# BoardTop.net
KiCad netlist of a schematic drawn in Altium Designer
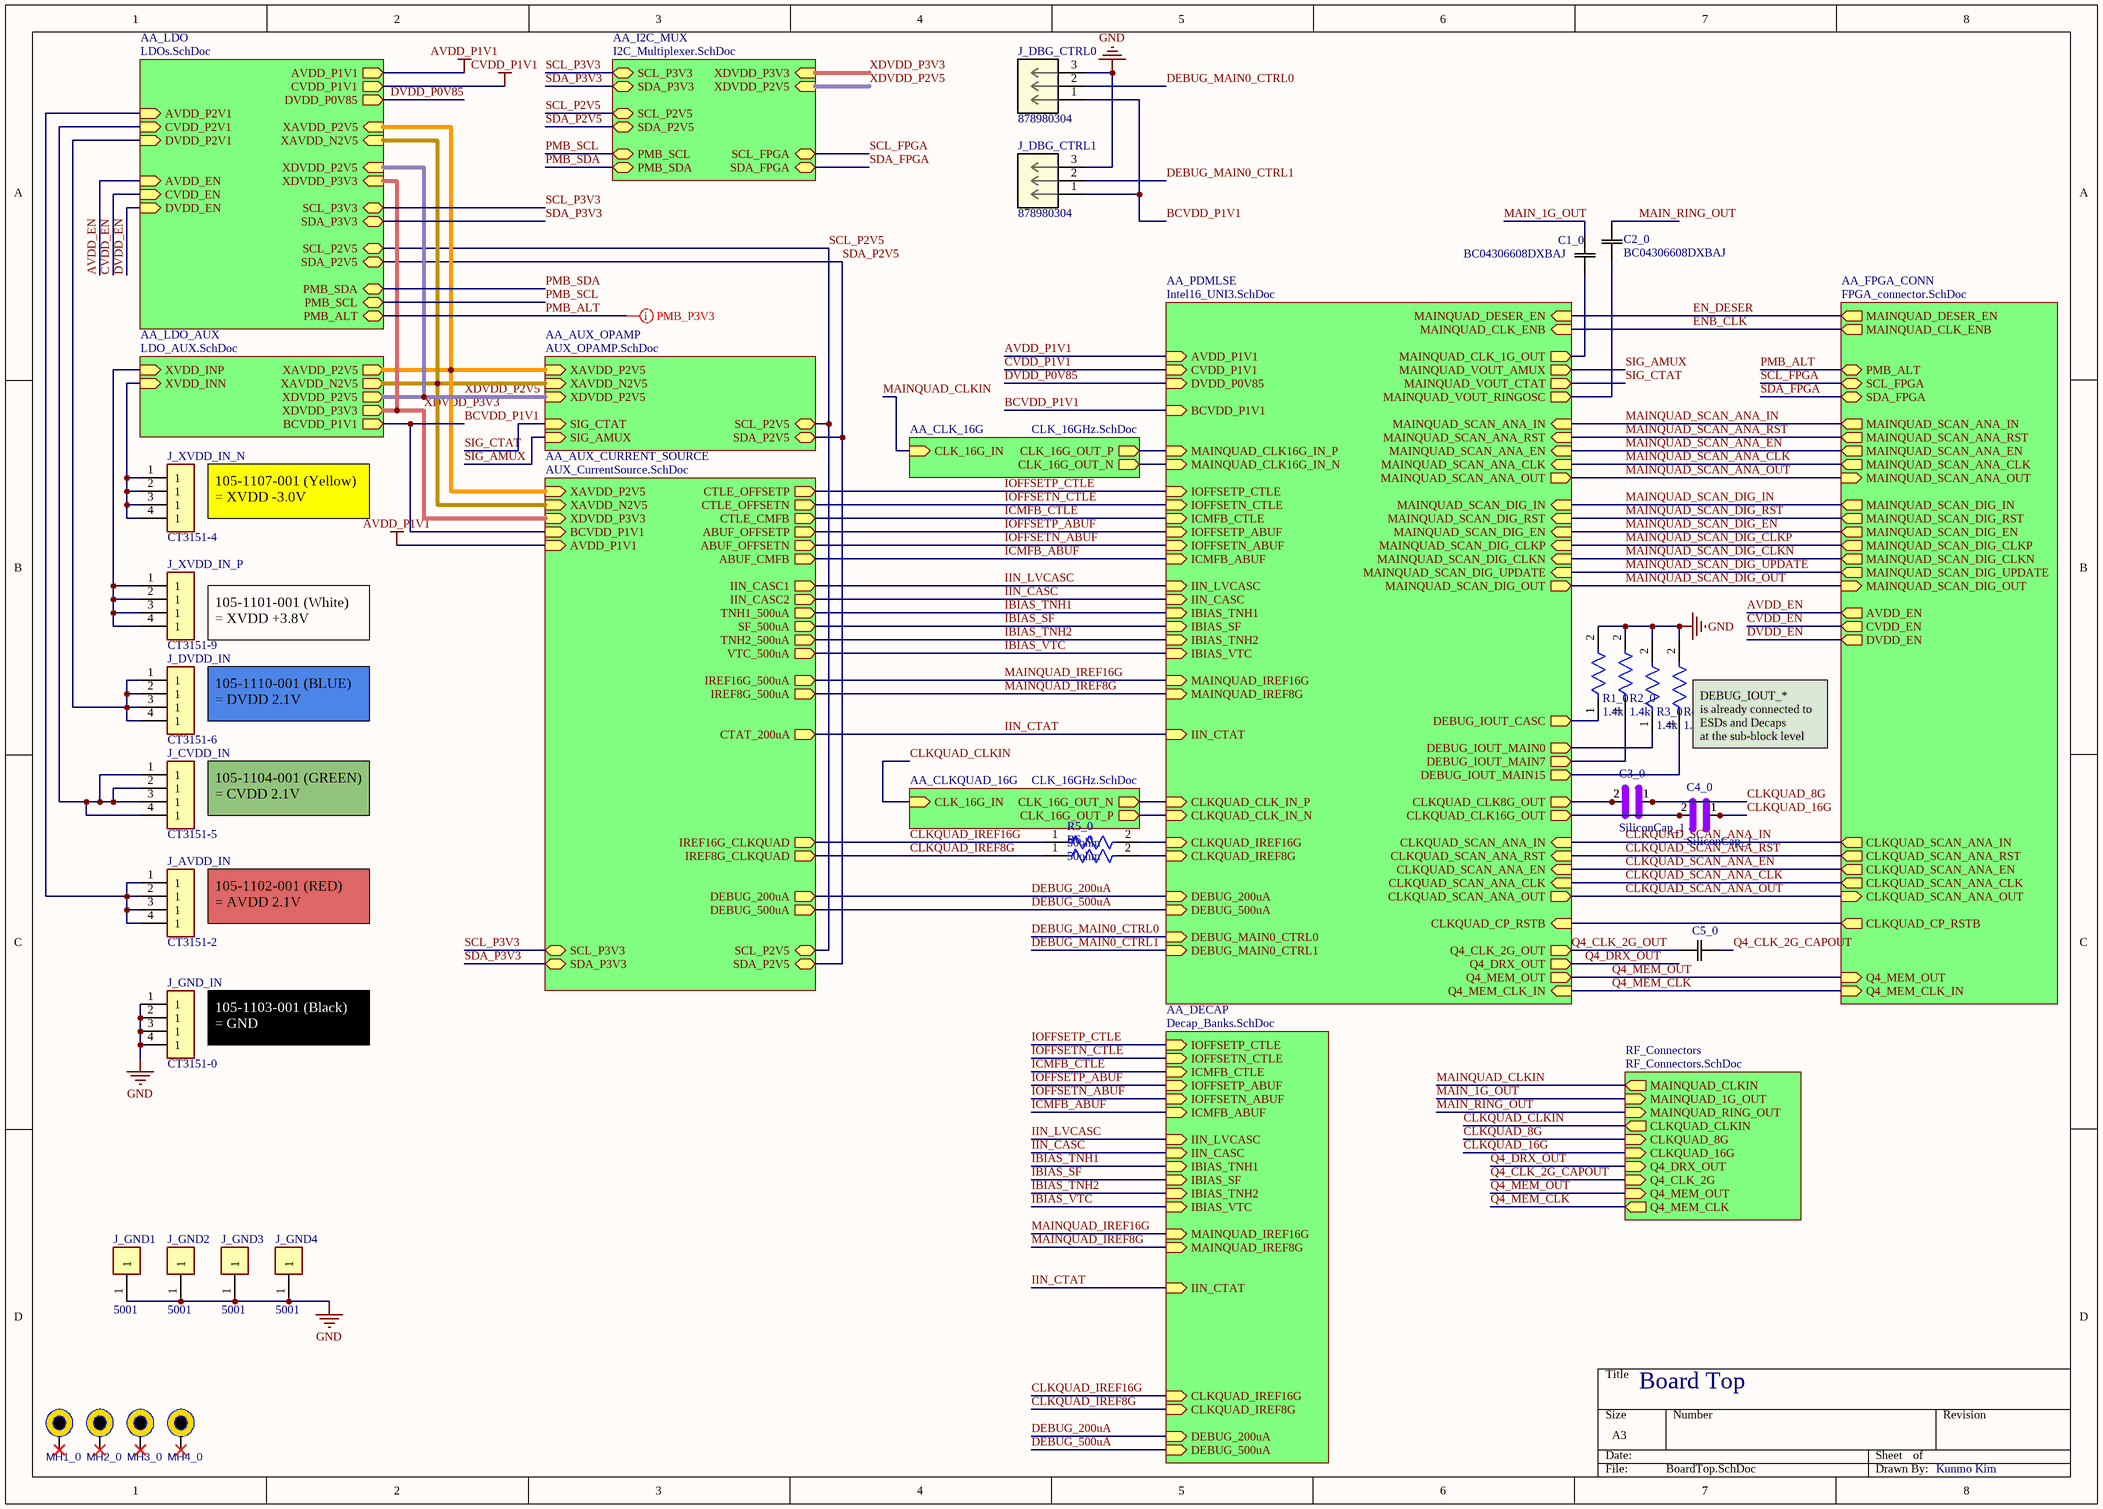
[diagram p0: BoardTop.SchDoc]

(export (version "E")
  (design (tool "Eeschema 10.0.6"))
  (components
    (comp (ref "C1_0")
      (value "BC04306608DXBAJ")
      (footprint "CAP_BC04_VIS")
      (description "No Description Available")
      (libsource (lib "BC04306608DXBAJ") (part "BC04306608DXBAJ"))
    )
    (comp (ref "C2_0")
      (value "BC04306608DXBAJ")
      (footprint "CAP_BC04_VIS")
      (description "No Description Available")
      (libsource (lib "BC04306608DXBAJ") (part "BC04306608DXBAJ"))
    )
    (comp (ref "C3_0")
      (value "SiliconCap_1")
      (footprint "0201-NOSILK")
      (description "939114492510-T3S from Murata")
      (libsource (lib "DC_Blocker") (part "SiliconCap_1"))
    )
    (comp (ref "C4_0")
      (value "SiliconCap_1")
      (footprint "0201-NOSILK")
      (description "939114492510-T3S from Murata")
      (libsource (lib "DC_Blocker") (part "SiliconCap_1"))
    )
    (comp (ref "C5_0")
      (value "BC04306608DXBAJ")
      (footprint "CAP_BC04_VIS")
      (description "No Description Available")
      (libsource (lib "BC04306608DXBAJ") (part "BC04306608DXBAJ"))
    )
    (comp (ref "J_AVDD_IN")
      (value "CT3151-2")
      (footprint "CALTEST_CT3151-2")
      (description "Banana Jack Connector Standard Banana Solder Red")
      (fields (field (name "MF") "Cal Test"))
      (libsource (lib "CT3151-2") (part "CT3151-2"))
    )
    (comp (ref "J_CVDD_IN")
      (value "CT3151-5")
      (footprint "CALTEST_CT3151-2")
      (description "Banana Jack Connector Standard Banana Solder Green")
      (fields (field (name "MF") "Cal Test") (field (name "MP") "CT3151-2"))
      (libsource (lib "CT3151-2") (part "CT3151-5"))
    )
    (comp (ref "J_DBG_CTRL0")
      (value "878980304")
      (footprint "CONN03_87898_M-5p84_MOL")
      (description "No Description Available")
      (libsource (lib "878980304") (part "878980304"))
    )
    (comp (ref "J_DBG_CTRL1")
      (value "878980304")
      (footprint "CONN03_87898_M-5p84_MOL")
      (description "No Description Available")
      (libsource (lib "878980304") (part "878980304"))
    )
    (comp (ref "J_DVDD_IN")
      (value "CT3151-6")
      (footprint "CALTEST_CT3151-2")
      (description "Banana Jack Connector Standard Banana Solder Green")
      (fields (field (name "MF") "Cal Test") (field (name "MP") "CT3151-2"))
      (libsource (lib "CT3151-2") (part "CT3151-6"))
    )
    (comp (ref "J_GND1")
      (value "5001")
      (footprint "FP-5001-MFG")
      (description "PC TEST POINT MINIATURE BLACK")
      (libsource (lib "TP_5001") (part "CMP-2000-05181-2"))
    )
    (comp (ref "J_GND2")
      (value "5001")
      (footprint "FP-5001-MFG")
      (description "PC TEST POINT MINIATURE BLACK")
      (libsource (lib "TP_5001") (part "CMP-2000-05181-2"))
    )
    (comp (ref "J_GND3")
      (value "5001")
      (footprint "FP-5001-MFG")
      (description "PC TEST POINT MINIATURE BLACK")
      (libsource (lib "TP_5001") (part "CMP-2000-05181-2"))
    )
    (comp (ref "J_GND4")
      (value "5001")
      (footprint "FP-5001-MFG")
      (description "PC TEST POINT MINIATURE BLACK")
      (libsource (lib "TP_5001") (part "CMP-2000-05181-2"))
    )
    (comp (ref "J_GND_IN")
      (value "CT3151-0")
      (footprint "CALTEST_CT3151-0")
      (description "Banana Jack Connector Standard Banana Solder Black")
      (fields (field (name "MF") "Cal Test") (field (name "MP") "CT3151-2"))
      (libsource (lib "CT3151-2") (part "CT3151-0"))
    )
    (comp (ref "J_XVDD_IN_N")
      (value "CT3151-4")
      (footprint "CALTEST_CT3151-2")
      (description "Banana Jack Connector Standard Banana Solder Yellow")
      (fields (field (name "MF") "Cal Test") (field (name "MP") "CT3151-2"))
      (libsource (lib "CT3151-2") (part "CT3151-4"))
    )
    (comp (ref "J_XVDD_IN_P")
      (value "CT3151-9")
      (footprint "CALTEST_CT3151-2")
      (description "Banana Jack Connector Standard Banana Solder White")
      (fields (field (name "MF") "Cal Test") (field (name "MP") "CT3151-2"))
      (libsource (lib "CT3151-2") (part "CT3151-9"))
    )
    (comp (ref "MH1_0")
      (value "MTG")
      (footprint "MTG-3.2/6.5-PTH")
      (description "Mounting hole")
      (libsource (lib "BRK8305") (part "MTG"))
    )
    (comp (ref "MH2_0")
      (value "MTG")
      (footprint "MTG-3.2/6.5-PTH")
      (description "Mounting hole")
      (libsource (lib "BRK8305") (part "MTG"))
    )
    (comp (ref "MH3_0")
      (value "MTG")
      (footprint "MTG-3.2/6.5-PTH")
      (description "Mounting hole")
      (libsource (lib "BRK8305") (part "MTG"))
    )
    (comp (ref "MH4_0")
      (value "MTG")
      (footprint "MTG-3.2/6.5-PTH")
      (description "Mounting hole")
      (libsource (lib "BRK8305") (part "MTG"))
    )
    (comp (ref "R1_0")
      (value "1.4k")
      (footprint "FP-CRCW1206-e3-IPC_B")
      (description "RES Thick Film, 1.4kΩ, 1%, 0.25W, 100ppm/°C, 1206")
      (fields (field (name "TOLERANCE") "1%"))
      (libsource (lib "resistor_1206_1p4k") (part "CMP-2003-01885-2"))
    )
    (comp (ref "R2_0")
      (value "1.4k")
      (footprint "FP-CRCW1206-e3-IPC_B")
      (description "RES Thick Film, 1.4kΩ, 1%, 0.25W, 100ppm/°C, 1206")
      (fields (field (name "TOLERANCE") "1%"))
      (libsource (lib "resistor_1206_1p4k") (part "CMP-2003-01885-2"))
    )
    (comp (ref "R3_0")
      (value "1.4k")
      (footprint "FP-CRCW1206-e3-IPC_B")
      (description "RES Thick Film, 1.4kΩ, 1%, 0.25W, 100ppm/°C, 1206")
      (fields (field (name "TOLERANCE") "1%"))
      (libsource (lib "resistor_1206_1p4k") (part "CMP-2003-01885-2"))
    )
    (comp (ref "R4_0")
      (value "1.4k")
      (footprint "FP-CRCW1206-e3-IPC_B")
      (description "RES Thick Film, 1.4kΩ, 1%, 0.25W, 100ppm/°C, 1206")
      (fields (field (name "TOLERANCE") "1%"))
      (libsource (lib "resistor_1206_1p4k") (part "CMP-2003-01885-2"))
    )
    (comp (ref "R5_0")
      (value "50ohm")
      (footprint "FP-RT0402-0_35-IPC_A")
      (fields (field (name "TOLERANCE") "0.1%"))
      (libsource (lib "resistor_50ohm_0402_0p1ptol") (part "1029c3af85768c4190bb7ad29bc67b5"))
    )
    (comp (ref "R6_0")
      (value "50ohm")
      (footprint "FP-RT0402-0_35-IPC_A")
      (fields (field (name "TOLERANCE") "0.1%"))
      (libsource (lib "resistor_50ohm_0402_0p1ptol") (part "1029c3af85768c4190bb7ad29bc67b5"))
    )
  )
  (nets
    (net (code "2") (name "/AVDD_P2V1") (class "Default")
      (node (ref "J_AVDD_IN") (pin "1") (pinfunction "1_1") (pintype "passive"))
      (node (ref "J_AVDD_IN") (pin "2") (pinfunction "1_2") (pintype "passive"))
      (node (ref "J_AVDD_IN") (pin "3") (pinfunction "1_3") (pintype "passive"))
      (node (ref "J_AVDD_IN") (pin "4") (pinfunction "1_4") (pintype "passive"))
    )
    (net (code "3") (name "/BCVDD_P1V1") (class "Default")
      (node (ref "J_DBG_CTRL0") (pin "1") (pinfunction "1_1") (pintype "passive"))
      (node (ref "J_DBG_CTRL1") (pin "1") (pinfunction "1_1") (pintype "passive"))
    )
    (net (code "4") (name "/CLKQUAD_8G") (class "Default")
      (node (ref "C3_0") (pin "1") (pinfunction "1_1") (pintype "passive"))
    )
    (net (code "5") (name "/CLKQUAD_16G") (class "Default")
      (node (ref "C4_0") (pin "1") (pinfunction "1_1") (pintype "passive"))
    )
    (net (code "6") (name "/CLKQUAD_CLK8G_OUT") (class "Default")
      (node (ref "C3_0") (pin "2") (pinfunction "2_2") (pintype "passive"))
    )
    (net (code "7") (name "/CLKQUAD_CLK16G_OUT") (class "Default")
      (node (ref "C4_0") (pin "2") (pinfunction "2_2") (pintype "passive"))
    )
    (net (code "10") (name "/CLKQUAD_IREF8G") (class "Default")
      (node (ref "R6_0") (pin "1") (pinfunction "1_1") (pintype "passive"))
    )
    (net (code "11") (name "/CLKQUAD_IREF8G_1") (class "Default")
      (node (ref "R6_0") (pin "2") (pinfunction "2_2") (pintype "passive"))
    )
    (net (code "12") (name "/CLKQUAD_IREF16G") (class "Default")
      (node (ref "R5_0") (pin "1") (pinfunction "1_1") (pintype "passive"))
    )
    (net (code "13") (name "/CLKQUAD_IREF16G_1") (class "Default")
      (node (ref "R5_0") (pin "2") (pinfunction "2_2") (pintype "passive"))
    )
    (net (code "24") (name "/CVDD_P2V1") (class "Default")
      (node (ref "J_CVDD_IN") (pin "1") (pinfunction "1_1") (pintype "passive"))
      (node (ref "J_CVDD_IN") (pin "2") (pinfunction "1_2") (pintype "passive"))
      (node (ref "J_CVDD_IN") (pin "3") (pinfunction "1_3") (pintype "passive"))
      (node (ref "J_CVDD_IN") (pin "4") (pinfunction "1_4") (pintype "passive"))
    )
    (net (code "27") (name "/DEBUG_IOUT_CASC") (class "Default")
      (node (ref "R1_0") (pin "1") (pinfunction "1_1") (pintype "passive"))
    )
    (net (code "28") (name "/DEBUG_IOUT_MAIN0") (class "Default")
      (node (ref "R3_0") (pin "1") (pinfunction "1_1") (pintype "passive"))
    )
    (net (code "29") (name "/DEBUG_IOUT_MAIN7") (class "Default")
      (node (ref "R2_0") (pin "1") (pinfunction "1_1") (pintype "passive"))
    )
    (net (code "30") (name "/DEBUG_IOUT_MAIN15") (class "Default")
      (node (ref "R4_0") (pin "1") (pinfunction "1_1") (pintype "passive"))
    )
    (net (code "31") (name "/DEBUG_MAIN0_CTRL0") (class "Default")
      (node (ref "J_DBG_CTRL0") (pin "2") (pinfunction "2_2") (pintype "passive"))
    )
    (net (code "32") (name "/DEBUG_MAIN0_CTRL1") (class "Default")
      (node (ref "J_DBG_CTRL1") (pin "2") (pinfunction "2_2") (pintype "passive"))
    )
    (net (code "35") (name "/DVDD_P2V1") (class "Default")
      (node (ref "J_DVDD_IN") (pin "1") (pinfunction "1_1") (pintype "passive"))
      (node (ref "J_DVDD_IN") (pin "2") (pinfunction "1_2") (pintype "passive"))
      (node (ref "J_DVDD_IN") (pin "3") (pinfunction "1_3") (pintype "passive"))
      (node (ref "J_DVDD_IN") (pin "4") (pinfunction "1_4") (pintype "passive"))
    )
    (net (code "52") (name "/MAINQUAD_CLK_1G_OUT") (class "Default")
      (node (ref "C1_0") (pin "1") (pinfunction "1_1") (pintype "passive"))
    )
    (net (code "67") (name "/MAINQUAD_VOUT_RINGOSC") (class "Default")
      (node (ref "C2_0") (pin "1") (pinfunction "1_1") (pintype "passive"))
    )
    (net (code "68") (name "/MAIN_1G_OUT") (class "Default")
      (node (ref "C1_0") (pin "2") (pinfunction "2_2") (pintype "passive"))
    )
    (net (code "69") (name "/MAIN_RING_OUT") (class "Default")
      (node (ref "C2_0") (pin "2") (pinfunction "2_2") (pintype "passive"))
    )
    (net (code "73") (name "/Q4_CLK_2G_CAPOUT") (class "Default")
      (node (ref "C5_0") (pin "2") (pinfunction "2_2") (pintype "passive"))
    )
    (net (code "74") (name "/Q4_CLK_2G_OUT") (class "Default")
      (node (ref "C5_0") (pin "1") (pinfunction "1_1") (pintype "passive"))
    )
    (net (code "90") (name "/XVDD_INN") (class "Default")
      (node (ref "J_XVDD_IN_N") (pin "1") (pinfunction "1_1") (pintype "passive"))
      (node (ref "J_XVDD_IN_N") (pin "2") (pinfunction "1_2") (pintype "passive"))
      (node (ref "J_XVDD_IN_N") (pin "3") (pinfunction "1_3") (pintype "passive"))
      (node (ref "J_XVDD_IN_N") (pin "4") (pinfunction "1_4") (pintype "passive"))
    )
    (net (code "91") (name "/XVDD_INP") (class "Default")
      (node (ref "J_XVDD_IN_P") (pin "1") (pinfunction "1_1") (pintype "passive"))
      (node (ref "J_XVDD_IN_P") (pin "2") (pinfunction "1_2") (pintype "passive"))
      (node (ref "J_XVDD_IN_P") (pin "3") (pinfunction "1_3") (pintype "passive"))
      (node (ref "J_XVDD_IN_P") (pin "4") (pinfunction "1_4") (pintype "passive"))
    )
    (net (code "94") (name "GND") (class "Default")
      (node (ref "J_DBG_CTRL0") (pin "3") (pinfunction "3_3") (pintype "passive"))
      (node (ref "J_DBG_CTRL1") (pin "3") (pinfunction "3_3") (pintype "passive"))
      (node (ref "J_GND1") (pin "1") (pinfunction "1_1") (pintype "passive"))
      (node (ref "J_GND2") (pin "1") (pinfunction "1_1") (pintype "passive"))
      (node (ref "J_GND3") (pin "1") (pinfunction "1_1") (pintype "passive"))
      (node (ref "J_GND4") (pin "1") (pinfunction "1_1") (pintype "passive"))
      (node (ref "J_GND_IN") (pin "1") (pinfunction "1_1") (pintype "passive"))
      (node (ref "J_GND_IN") (pin "2") (pinfunction "1_2") (pintype "passive"))
      (node (ref "J_GND_IN") (pin "3") (pinfunction "1_3") (pintype "passive"))
      (node (ref "J_GND_IN") (pin "4") (pinfunction "1_4") (pintype "passive"))
      (node (ref "R1_0") (pin "2") (pinfunction "2_2") (pintype "passive"))
      (node (ref "R2_0") (pin "2") (pinfunction "2_2") (pintype "passive"))
      (node (ref "R3_0") (pin "2") (pinfunction "2_2") (pintype "passive"))
      (node (ref "R4_0") (pin "2") (pinfunction "2_2") (pintype "passive"))
    )
    (net (code "95") (name "unconnected-(MH1_0-Pad1)") (class "Default")
      (node (ref "MH1_0") (pin "1") (pinfunction "1_1") (pintype "passive+no_connect"))
    )
    (net (code "96") (name "unconnected-(MH2_0-Pad1)") (class "Default")
      (node (ref "MH2_0") (pin "1") (pinfunction "1_1") (pintype "passive+no_connect"))
    )
    (net (code "97") (name "unconnected-(MH3_0-Pad1)") (class "Default")
      (node (ref "MH3_0") (pin "1") (pinfunction "1_1") (pintype "passive+no_connect"))
    )
    (net (code "98") (name "unconnected-(MH4_0-Pad1)") (class "Default")
      (node (ref "MH4_0") (pin "1") (pinfunction "1_1") (pintype "passive+no_connect"))
    )
  )
)
